# motion_daughter.net
KiCad netlist of a schematic drawn in EAGLE
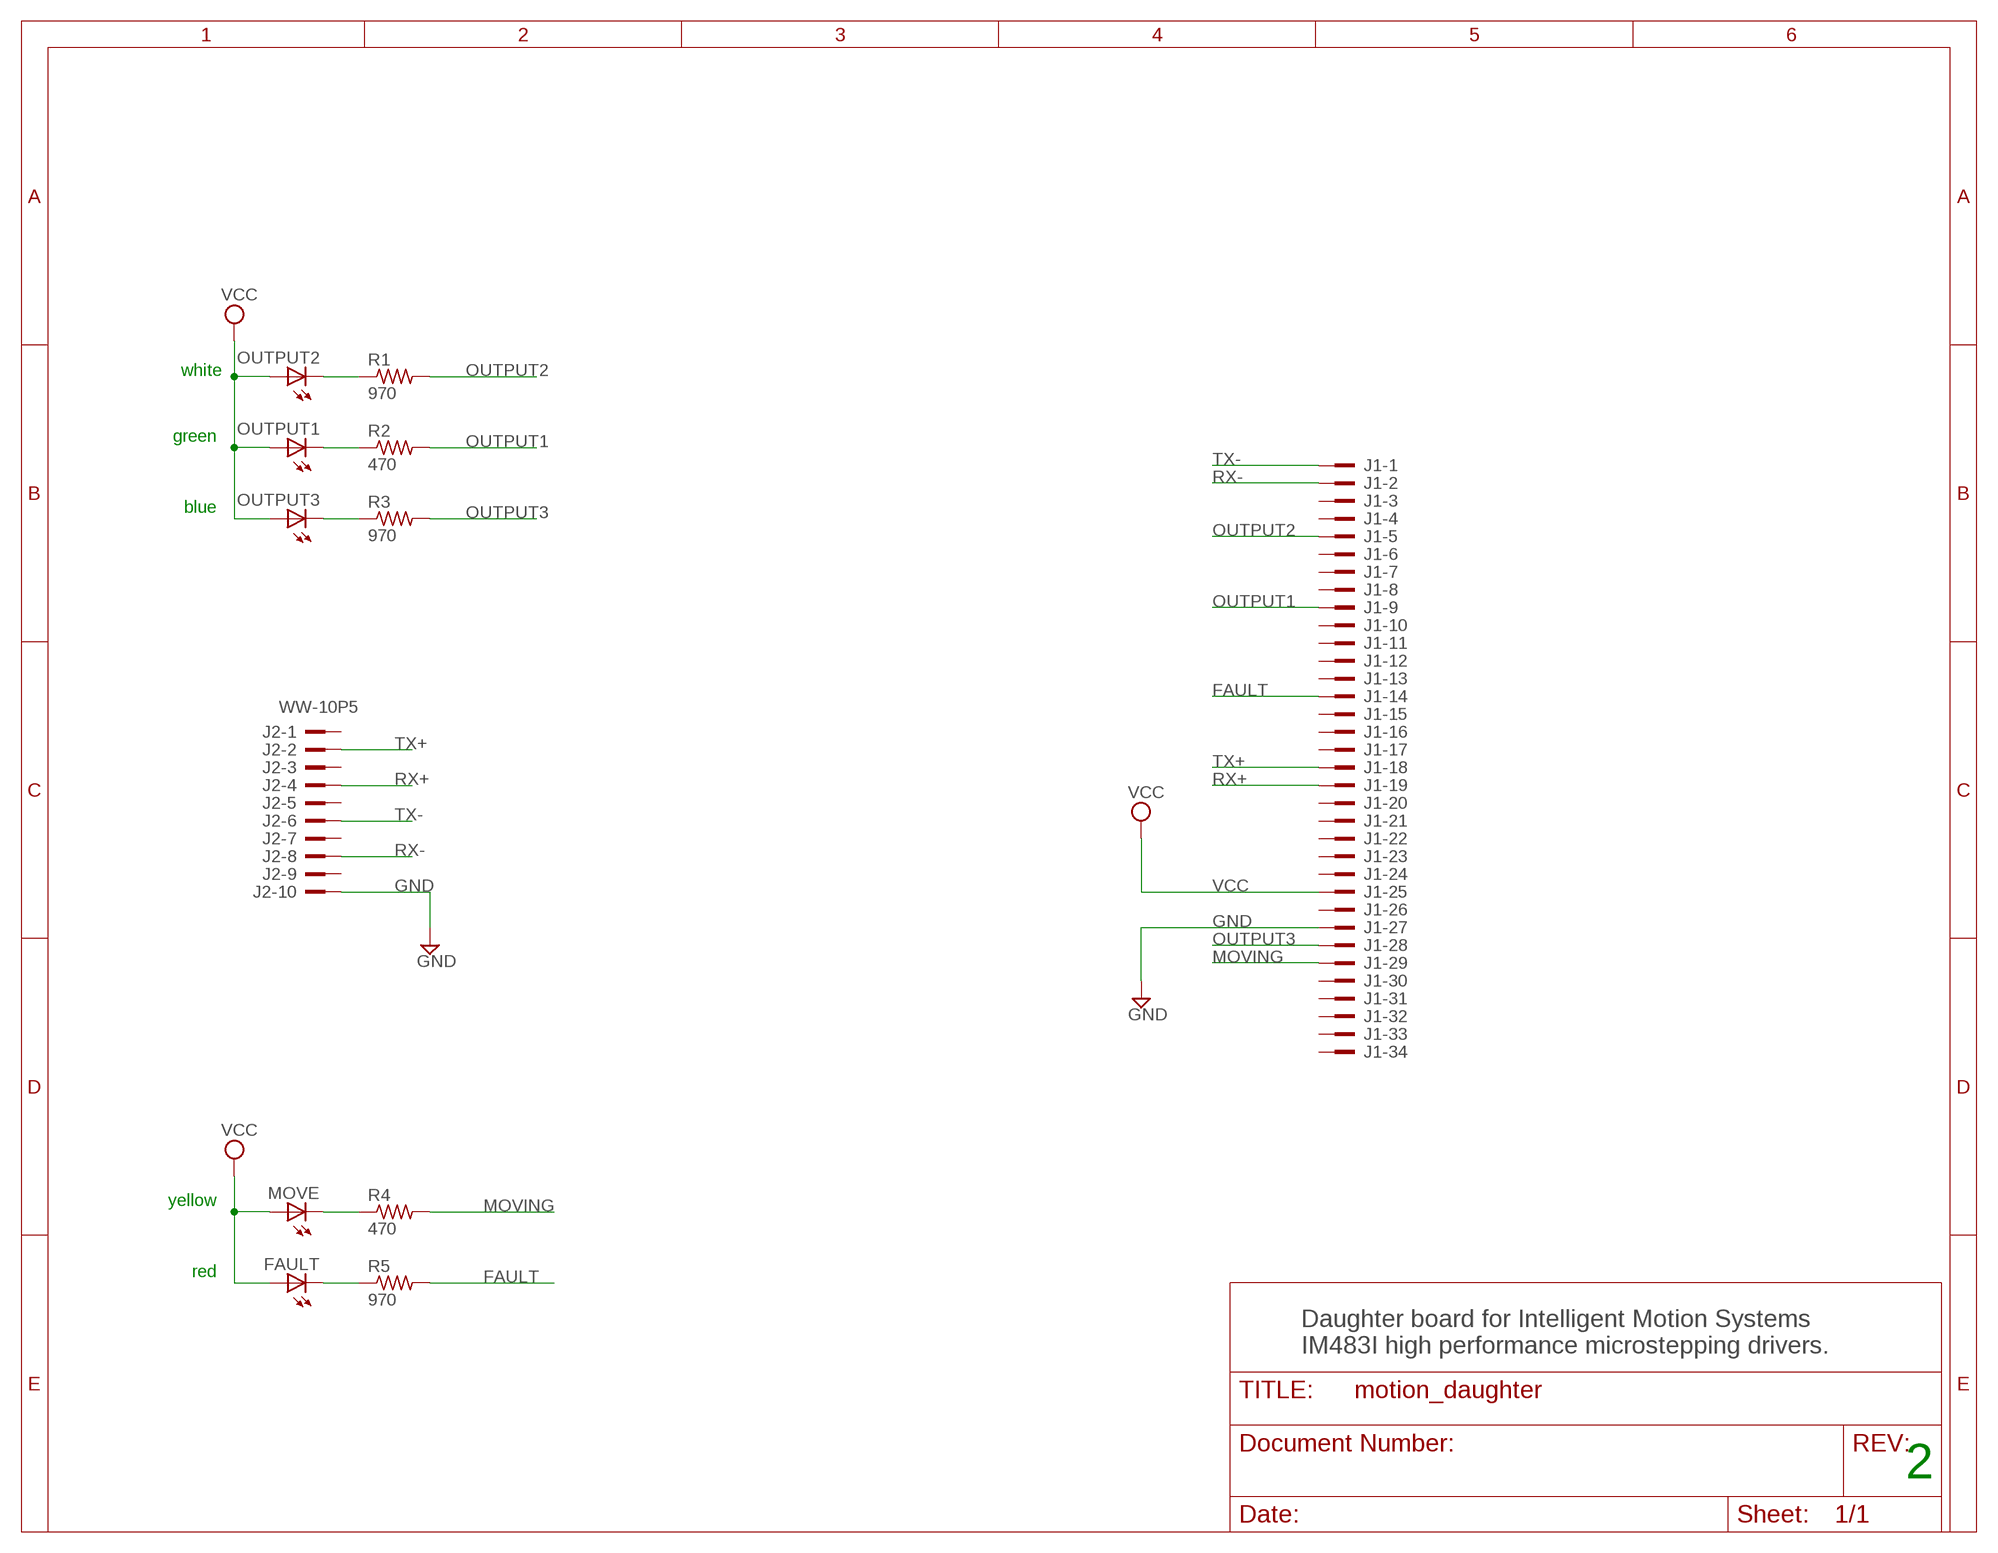
[diagram p0: schematic, sheet 1]

(export (version "E")
  (design (tool "Eeschema 10.0.6"))
  (components
    (comp (ref "FAULT")
      (value "LED3MM")
      (footprint "eagle-import:LED3MM")
      (libsource (lib "eagle-import") (part "LED3MM"))
    )
    (comp (ref "J1")
      (value "WW-34P-SPECIALIM483I_HEADER")
      (footprint "eagle-import:PAK100_2500-34")
      (libsource (lib "eagle-import") (part "WW-34P-SPECIALIM483I_HEADER"))
    )
    (comp (ref "J2")
      (value "WW-10P5")
      (footprint "eagle-import:PAK100_2500-5-10")
      (libsource (lib "eagle-import") (part "WW-10P5"))
    )
    (comp (ref "MOVE")
      (value "LED3MM")
      (footprint "eagle-import:LED3MM")
      (libsource (lib "eagle-import") (part "LED3MM"))
    )
    (comp (ref "OUTPUT1")
      (value "LED3MM")
      (footprint "eagle-import:LED3MM")
      (libsource (lib "eagle-import") (part "LED3MM"))
    )
    (comp (ref "OUTPUT2")
      (value "LED3MM")
      (footprint "eagle-import:LED3MM")
      (libsource (lib "eagle-import") (part "LED3MM"))
    )
    (comp (ref "OUTPUT3")
      (value "LED3MM")
      (footprint "eagle-import:LED3MM")
      (libsource (lib "eagle-import") (part "LED3MM"))
    )
    (comp (ref "R1")
      (value "970")
      (footprint "eagle-import:0207_7")
      (libsource (lib "eagle-import") (part "R-US_0207/7"))
    )
    (comp (ref "R2")
      (value "470")
      (footprint "eagle-import:0207_7")
      (libsource (lib "eagle-import") (part "R-US_0207/7"))
    )
    (comp (ref "R3")
      (value "970")
      (footprint "eagle-import:0207_7")
      (libsource (lib "eagle-import") (part "R-US_0207/7"))
    )
    (comp (ref "R4")
      (value "470")
      (footprint "eagle-import:0207_7")
      (libsource (lib "eagle-import") (part "R-US_0207/7"))
    )
    (comp (ref "R5")
      (value "970")
      (footprint "eagle-import:0207_7")
      (libsource (lib "eagle-import") (part "R-US_0207/7"))
    )
  )
  (nets
    (net (code "1") (name "/FAULT") (class "Default")
      (node (ref "J1") (pin "P14") (pinfunction "KL_P14") (pintype "passive"))
      (node (ref "R5") (pin "2") (pinfunction "2_2") (pintype "passive"))
    )
    (net (code "2") (name "/MOVING") (class "Default")
      (node (ref "J1") (pin "P29") (pinfunction "KL_P29") (pintype "passive"))
      (node (ref "R4") (pin "2") (pinfunction "2_2") (pintype "passive"))
    )
    (net (code "3") (name "/OUTPUT1") (class "Default")
      (node (ref "J1") (pin "P9") (pinfunction "KL_P9") (pintype "passive"))
      (node (ref "R2") (pin "2") (pinfunction "2_2") (pintype "passive"))
    )
    (net (code "4") (name "/OUTPUT2") (class "Default")
      (node (ref "J1") (pin "P5") (pinfunction "KL_P5") (pintype "passive"))
      (node (ref "R1") (pin "2") (pinfunction "2_2") (pintype "passive"))
    )
    (net (code "5") (name "/OUTPUT3") (class "Default")
      (node (ref "J1") (pin "P28") (pinfunction "KL_P28") (pintype "passive"))
      (node (ref "R3") (pin "2") (pinfunction "2_2") (pintype "passive"))
    )
    (net (code "6") (name "/RX+") (class "Default")
      (node (ref "J1") (pin "P19") (pinfunction "KL_P19") (pintype "passive"))
      (node (ref "J2") (pin "4") (pinfunction "KL_4") (pintype "passive"))
    )
    (net (code "7") (name "/RX-") (class "Default")
      (node (ref "J1") (pin "P2") (pinfunction "KL_P2") (pintype "passive"))
      (node (ref "J2") (pin "8") (pinfunction "KL_8") (pintype "passive"))
    )
    (net (code "8") (name "/TX+") (class "Default")
      (node (ref "J1") (pin "P18") (pinfunction "KL_P18") (pintype "passive"))
      (node (ref "J2") (pin "2") (pinfunction "KL_2") (pintype "passive"))
    )
    (net (code "9") (name "/TX-") (class "Default")
      (node (ref "J1") (pin "P1") (pinfunction "KL_P1") (pintype "passive"))
      (node (ref "J2") (pin "6") (pinfunction "KL_6") (pintype "passive"))
    )
    (net (code "10") (name "GND") (class "Default")
      (node (ref "J1") (pin "P27") (pinfunction "KL_P27") (pintype "passive"))
      (node (ref "J2") (pin "10") (pinfunction "KL_10") (pintype "passive"))
    )
    (net (code "11") (name "Net-(FAULT-C)") (class "Default")
      (node (ref "FAULT") (pin "K") (pinfunction "C_K") (pintype "passive"))
      (node (ref "R5") (pin "1") (pinfunction "1_1") (pintype "passive"))
    )
    (net (code "12") (name "Net-(MOVE-C)") (class "Default")
      (node (ref "MOVE") (pin "K") (pinfunction "C_K") (pintype "passive"))
      (node (ref "R4") (pin "1") (pinfunction "1_1") (pintype "passive"))
    )
    (net (code "13") (name "Net-(OUTPUT1-C)") (class "Default")
      (node (ref "OUTPUT1") (pin "K") (pinfunction "C_K") (pintype "passive"))
      (node (ref "R2") (pin "1") (pinfunction "1_1") (pintype "passive"))
    )
    (net (code "14") (name "Net-(OUTPUT2-C)") (class "Default")
      (node (ref "OUTPUT2") (pin "K") (pinfunction "C_K") (pintype "passive"))
      (node (ref "R1") (pin "1") (pinfunction "1_1") (pintype "passive"))
    )
    (net (code "15") (name "Net-(OUTPUT3-C)") (class "Default")
      (node (ref "OUTPUT3") (pin "K") (pinfunction "C_K") (pintype "passive"))
      (node (ref "R3") (pin "1") (pinfunction "1_1") (pintype "passive"))
    )
    (net (code "16") (name "VCC") (class "Default")
      (node (ref "FAULT") (pin "A") (pinfunction "A_A") (pintype "passive"))
      (node (ref "J1") (pin "P25") (pinfunction "KL_P25") (pintype "passive"))
      (node (ref "MOVE") (pin "A") (pinfunction "A_A") (pintype "passive"))
      (node (ref "OUTPUT1") (pin "A") (pinfunction "A_A") (pintype "passive"))
      (node (ref "OUTPUT2") (pin "A") (pinfunction "A_A") (pintype "passive"))
      (node (ref "OUTPUT3") (pin "A") (pinfunction "A_A") (pintype "passive"))
    )
    (net (code "17") (name "unconnected-(J1AA-KL-PadP33)") (class "Default")
      (node (ref "J1") (pin "P33") (pinfunction "KL_P33") (pintype "passive"))
    )
    (net (code "18") (name "unconnected-(J1AB-KL-PadP34)") (class "Default")
      (node (ref "J1") (pin "P34") (pinfunction "KL_P34") (pintype "passive"))
    )
    (net (code "19") (name "unconnected-(J1AC-KL-PadP4)") (class "Default")
      (node (ref "J1") (pin "P4") (pinfunction "KL_P4") (pintype "passive"))
    )
    (net (code "20") (name "unconnected-(J1AE-KL-PadP6)") (class "Default")
      (node (ref "J1") (pin "P6") (pinfunction "KL_P6") (pintype "passive"))
    )
    (net (code "21") (name "unconnected-(J1AF-KL-PadP7)") (class "Default")
      (node (ref "J1") (pin "P7") (pinfunction "KL_P7") (pintype "passive"))
    )
    (net (code "22") (name "unconnected-(J1AG-KL-PadP8)") (class "Default")
      (node (ref "J1") (pin "P8") (pinfunction "KL_P8") (pintype "passive"))
    )
    (net (code "23") (name "unconnected-(J1B-KL-PadP10)") (class "Default")
      (node (ref "J1") (pin "P10") (pinfunction "KL_P10") (pintype "passive"))
    )
    (net (code "24") (name "unconnected-(J1C-KL-PadP11)") (class "Default")
      (node (ref "J1") (pin "P11") (pinfunction "KL_P11") (pintype "passive"))
    )
    (net (code "25") (name "unconnected-(J1D-KL-PadP12)") (class "Default")
      (node (ref "J1") (pin "P12") (pinfunction "KL_P12") (pintype "passive"))
    )
    (net (code "26") (name "unconnected-(J1E-KL-PadP13)") (class "Default")
      (node (ref "J1") (pin "P13") (pinfunction "KL_P13") (pintype "passive"))
    )
    (net (code "27") (name "unconnected-(J1G-KL-PadP15)") (class "Default")
      (node (ref "J1") (pin "P15") (pinfunction "KL_P15") (pintype "passive"))
    )
    (net (code "28") (name "unconnected-(J1H-KL-PadP16)") (class "Default")
      (node (ref "J1") (pin "P16") (pinfunction "KL_P16") (pintype "passive"))
    )
    (net (code "29") (name "unconnected-(J1I-KL-PadP17)") (class "Default")
      (node (ref "J1") (pin "P17") (pinfunction "KL_P17") (pintype "passive"))
    )
    (net (code "30") (name "unconnected-(J1M-KL-PadP20)") (class "Default")
      (node (ref "J1") (pin "P20") (pinfunction "KL_P20") (pintype "passive"))
    )
    (net (code "31") (name "unconnected-(J1N-KL-PadP21)") (class "Default")
      (node (ref "J1") (pin "P21") (pinfunction "KL_P21") (pintype "passive"))
    )
    (net (code "32") (name "unconnected-(J1O-KL-PadP22)") (class "Default")
      (node (ref "J1") (pin "P22") (pinfunction "KL_P22") (pintype "passive"))
    )
    (net (code "33") (name "unconnected-(J1P-KL-PadP23)") (class "Default")
      (node (ref "J1") (pin "P23") (pinfunction "KL_P23") (pintype "passive"))
    )
    (net (code "34") (name "unconnected-(J1Q-KL-PadP24)") (class "Default")
      (node (ref "J1") (pin "P24") (pinfunction "KL_P24") (pintype "passive"))
    )
    (net (code "35") (name "unconnected-(J1S-KL-PadP26)") (class "Default")
      (node (ref "J1") (pin "P26") (pinfunction "KL_P26") (pintype "passive"))
    )
    (net (code "36") (name "unconnected-(J1W-KL-PadP3)") (class "Default")
      (node (ref "J1") (pin "P3") (pinfunction "KL_P3") (pintype "passive"))
    )
    (net (code "37") (name "unconnected-(J1X-KL-PadP30)") (class "Default")
      (node (ref "J1") (pin "P30") (pinfunction "KL_P30") (pintype "passive"))
    )
    (net (code "38") (name "unconnected-(J1Y-KL-PadP31)") (class "Default")
      (node (ref "J1") (pin "P31") (pinfunction "KL_P31") (pintype "passive"))
    )
    (net (code "39") (name "unconnected-(J1Z-KL-PadP32)") (class "Default")
      (node (ref "J1") (pin "P32") (pinfunction "KL_P32") (pintype "passive"))
    )
    (net (code "40") (name "unconnected-(J2A-KL-Pad1)") (class "Default")
      (node (ref "J2") (pin "1") (pinfunction "KL_1") (pintype "passive"))
    )
    (net (code "41") (name "unconnected-(J2D-KL-Pad3)") (class "Default")
      (node (ref "J2") (pin "3") (pinfunction "KL_3") (pintype "passive"))
    )
    (net (code "42") (name "unconnected-(J2F-KL-Pad5)") (class "Default")
      (node (ref "J2") (pin "5") (pinfunction "KL_5") (pintype "passive"))
    )
    (net (code "43") (name "unconnected-(J2H-KL-Pad7)") (class "Default")
      (node (ref "J2") (pin "7") (pinfunction "KL_7") (pintype "passive"))
    )
    (net (code "44") (name "unconnected-(J2J-KL-Pad9)") (class "Default")
      (node (ref "J2") (pin "9") (pinfunction "KL_9") (pintype "passive"))
    )
  )
)
